# Shield_ver2.net
KiCad netlist of a schematic drawn in EAGLE
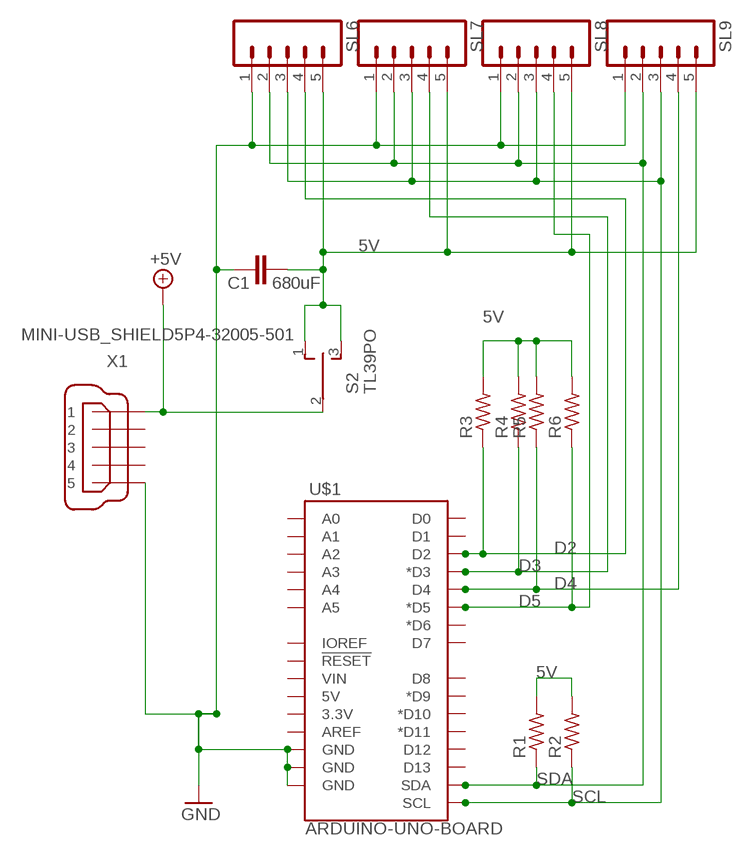
[diagram p0: schematic, sheet 1]

(export (version "E")
  (design (tool "Eeschema 10.0.6"))
  (components
    (comp (ref "C1")
      (value "680uF")
      (footprint "eagle-import:C5B2.5")
      (libsource (lib "eagle-import") (part "C5/2.5"))
    )
    (comp (ref "R1")
      (value "R-US_R0805")
      (footprint "eagle-import:R0805")
      (libsource (lib "eagle-import") (part "R-US_R0805"))
    )
    (comp (ref "R2")
      (value "R-US_R0805")
      (footprint "eagle-import:R0805")
      (libsource (lib "eagle-import") (part "R-US_R0805"))
    )
    (comp (ref "R3")
      (value "R-US_R0805")
      (footprint "eagle-import:R0805")
      (libsource (lib "eagle-import") (part "R-US_R0805"))
    )
    (comp (ref "R4")
      (value "R-US_R0805")
      (footprint "eagle-import:R0805")
      (libsource (lib "eagle-import") (part "R-US_R0805"))
    )
    (comp (ref "R5")
      (value "R-US_R0805")
      (footprint "eagle-import:R0805")
      (libsource (lib "eagle-import") (part "R-US_R0805"))
    )
    (comp (ref "R6")
      (value "R-US_R0805")
      (footprint "eagle-import:R0805")
      (libsource (lib "eagle-import") (part "R-US_R0805"))
    )
    (comp (ref "S2")
      (value "TL39PO")
      (footprint "eagle-import:TL3XPO")
      (libsource (lib "eagle-import") (part "TL39PO"))
    )
    (comp (ref "SL6")
      (value "M05")
      (footprint "eagle-import:05P")
      (libsource (lib "eagle-import") (part "M05"))
    )
    (comp (ref "SL7")
      (value "M05")
      (footprint "eagle-import:05P")
      (libsource (lib "eagle-import") (part "M05"))
    )
    (comp (ref "SL8")
      (value "M05")
      (footprint "eagle-import:05P")
      (libsource (lib "eagle-import") (part "M05"))
    )
    (comp (ref "SL9")
      (value "M05")
      (footprint "eagle-import:05P")
      (libsource (lib "eagle-import") (part "M05"))
    )
    (comp (ref "U$1")
      (value "ARDUINO-UNO-BOARD")
      (footprint "eagle-import:ARDUINO-UNO-BOARD")
      (libsource (lib "eagle-import") (part "ARDUINO-UNO-BOARD"))
    )
    (comp (ref "X1")
      (value "MINI-USB_SHIELD5P4-32005-501")
      (footprint "eagle-import:32005-501")
      (libsource (lib "eagle-import") (part "MINI-USB_SHIELD5P4-32005-501"))
    )
  )
  (nets
    (net (code "1") (name "+5V") (class "Default")
      (node (ref "S2") (pin "2") (pinfunction "P_2") (pintype "passive"))
      (node (ref "X1") (pin "1") (pinfunction "1_1") (pintype "passive"))
    )
    (net (code "2") (name "/5V") (class "Default")
      (node (ref "C1") (pin "2") (pinfunction "2_2") (pintype "passive"))
      (node (ref "R1") (pin "2") (pinfunction "2_2") (pintype "passive"))
      (node (ref "R2") (pin "2") (pinfunction "2_2") (pintype "passive"))
      (node (ref "R3") (pin "2") (pinfunction "2_2") (pintype "passive"))
      (node (ref "R4") (pin "2") (pinfunction "2_2") (pintype "passive"))
      (node (ref "R5") (pin "2") (pinfunction "2_2") (pintype "passive"))
      (node (ref "R6") (pin "2") (pinfunction "2_2") (pintype "passive"))
      (node (ref "S2") (pin "1") (pinfunction "O_1") (pintype "passive"))
      (node (ref "S2") (pin "3") (pinfunction "S_3") (pintype "passive"))
      (node (ref "SL6") (pin "5") (pinfunction "5_5") (pintype "passive"))
      (node (ref "SL7") (pin "5") (pinfunction "5_5") (pintype "passive"))
      (node (ref "SL8") (pin "5") (pinfunction "5_5") (pintype "passive"))
      (node (ref "SL9") (pin "5") (pinfunction "5_5") (pintype "passive"))
    )
    (net (code "3") (name "/D2") (class "Default")
      (node (ref "R3") (pin "1") (pinfunction "1_1") (pintype "passive"))
      (node (ref "SL6") (pin "4") (pinfunction "4_4") (pintype "passive"))
      (node (ref "U$1") (pin "D2") (pinfunction "D2_D2") (pintype "bidirectional"))
    )
    (net (code "4") (name "/D3") (class "Default")
      (node (ref "R4") (pin "1") (pinfunction "1_1") (pintype "passive"))
      (node (ref "SL7") (pin "4") (pinfunction "4_4") (pintype "passive"))
      (node (ref "U$1") (pin "D3") (pinfunction "*D3_D3") (pintype "bidirectional"))
    )
    (net (code "5") (name "/D4") (class "Default")
      (node (ref "R5") (pin "1") (pinfunction "1_1") (pintype "passive"))
      (node (ref "SL9") (pin "4") (pinfunction "4_4") (pintype "passive"))
      (node (ref "U$1") (pin "D4") (pinfunction "D4_D4") (pintype "bidirectional"))
    )
    (net (code "6") (name "/D5") (class "Default")
      (node (ref "R6") (pin "1") (pinfunction "1_1") (pintype "passive"))
      (node (ref "SL8") (pin "4") (pinfunction "4_4") (pintype "passive"))
      (node (ref "U$1") (pin "D5") (pinfunction "*D5_D5") (pintype "bidirectional"))
    )
    (net (code "7") (name "/SCL") (class "Default")
      (node (ref "R2") (pin "1") (pinfunction "1_1") (pintype "passive"))
      (node (ref "SL6") (pin "3") (pinfunction "3_3") (pintype "passive"))
      (node (ref "SL7") (pin "3") (pinfunction "3_3") (pintype "passive"))
      (node (ref "SL8") (pin "3") (pinfunction "3_3") (pintype "passive"))
      (node (ref "SL9") (pin "3") (pinfunction "3_3") (pintype "passive"))
      (node (ref "U$1") (pin "SCL") (pinfunction "SCL_SCL") (pintype "bidirectional"))
    )
    (net (code "8") (name "/SDA") (class "Default")
      (node (ref "R1") (pin "1") (pinfunction "1_1") (pintype "passive"))
      (node (ref "SL6") (pin "2") (pinfunction "2_2") (pintype "passive"))
      (node (ref "SL7") (pin "2") (pinfunction "2_2") (pintype "passive"))
      (node (ref "SL8") (pin "2") (pinfunction "2_2") (pintype "passive"))
      (node (ref "SL9") (pin "2") (pinfunction "2_2") (pintype "passive"))
      (node (ref "U$1") (pin "SDA") (pinfunction "SDA_SDA") (pintype "bidirectional"))
    )
    (net (code "9") (name "GND") (class "Default")
      (node (ref "C1") (pin "1") (pinfunction "1_1") (pintype "passive"))
      (node (ref "SL6") (pin "1") (pinfunction "1_1") (pintype "passive"))
      (node (ref "SL7") (pin "1") (pinfunction "1_1") (pintype "passive"))
      (node (ref "SL8") (pin "1") (pinfunction "1_1") (pintype "passive"))
      (node (ref "SL9") (pin "1") (pinfunction "1_1") (pintype "passive"))
      (node (ref "U$1") (pin "GND@1") (pinfunction "GND_GND@1") (pintype "bidirectional"))
      (node (ref "U$1") (pin "GND@2") (pinfunction "GND_GND@2") (pintype "bidirectional"))
      (node (ref "U$1") (pin "GND@3") (pinfunction "GND_GND@3") (pintype "bidirectional"))
      (node (ref "X1") (pin "5") (pinfunction "5_5") (pintype "passive"))
    )
    (net (code "10") (name "unconnected-(U$1-*D6-PadD6)") (class "Default")
      (node (ref "U$1") (pin "D6") (pinfunction "*D6_D6") (pintype "bidirectional"))
    )
    (net (code "11") (name "unconnected-(U$1-*D9-PadD9)") (class "Default")
      (node (ref "U$1") (pin "D9") (pinfunction "*D9_D9") (pintype "bidirectional"))
    )
    (net (code "12") (name "unconnected-(U$1-*D10-PadD10)") (class "Default")
      (node (ref "U$1") (pin "D10") (pinfunction "*D10_D10") (pintype "bidirectional"))
    )
    (net (code "13") (name "unconnected-(U$1-*D11-PadD11)") (class "Default")
      (node (ref "U$1") (pin "D11") (pinfunction "*D11_D11") (pintype "bidirectional"))
    )
    (net (code "14") (name "unconnected-(U$1-Pad3.3V)") (class "Default")
      (node (ref "U$1") (pin "3.3V") (pinfunction "3.3V_3.3V") (pintype "bidirectional"))
    )
    (net (code "15") (name "unconnected-(U$1-Pad5V)") (class "Default")
      (node (ref "U$1") (pin "5V") (pinfunction "5V_5V") (pintype "bidirectional"))
    )
    (net (code "16") (name "unconnected-(U$1-PadA0)") (class "Default")
      (node (ref "U$1") (pin "A0") (pinfunction "A0_A0") (pintype "bidirectional"))
    )
    (net (code "17") (name "unconnected-(U$1-PadA1)") (class "Default")
      (node (ref "U$1") (pin "A1") (pinfunction "A1_A1") (pintype "bidirectional"))
    )
    (net (code "18") (name "unconnected-(U$1-PadA2)") (class "Default")
      (node (ref "U$1") (pin "A2") (pinfunction "A2_A2") (pintype "bidirectional"))
    )
    (net (code "19") (name "unconnected-(U$1-PadA3)") (class "Default")
      (node (ref "U$1") (pin "A3") (pinfunction "A3_A3") (pintype "bidirectional"))
    )
    (net (code "20") (name "unconnected-(U$1-PadA4)") (class "Default")
      (node (ref "U$1") (pin "A4") (pinfunction "A4_A4") (pintype "bidirectional"))
    )
    (net (code "21") (name "unconnected-(U$1-PadA5)") (class "Default")
      (node (ref "U$1") (pin "A5") (pinfunction "A5_A5") (pintype "bidirectional"))
    )
    (net (code "22") (name "unconnected-(U$1-PadAREF)") (class "Default")
      (node (ref "U$1") (pin "AREF") (pinfunction "AREF_AREF") (pintype "bidirectional"))
    )
    (net (code "23") (name "unconnected-(U$1-PadD0)") (class "Default")
      (node (ref "U$1") (pin "D0") (pinfunction "D0_D0") (pintype "bidirectional"))
    )
    (net (code "24") (name "unconnected-(U$1-PadD1)") (class "Default")
      (node (ref "U$1") (pin "D1") (pinfunction "D1_D1") (pintype "bidirectional"))
    )
    (net (code "25") (name "unconnected-(U$1-PadD7)") (class "Default")
      (node (ref "U$1") (pin "D7") (pinfunction "D7_D7") (pintype "bidirectional"))
    )
    (net (code "26") (name "unconnected-(U$1-PadD8)") (class "Default")
      (node (ref "U$1") (pin "D8") (pinfunction "D8_D8") (pintype "bidirectional"))
    )
    (net (code "27") (name "unconnected-(U$1-PadD12)") (class "Default")
      (node (ref "U$1") (pin "D12") (pinfunction "D12_D12") (pintype "bidirectional"))
    )
    (net (code "28") (name "unconnected-(U$1-PadD13)") (class "Default")
      (node (ref "U$1") (pin "D13") (pinfunction "D13_D13") (pintype "bidirectional"))
    )
    (net (code "29") (name "unconnected-(U$1-PadIOREF)") (class "Default")
      (node (ref "U$1") (pin "IOREF") (pinfunction "IOREF_IOREF") (pintype "bidirectional"))
    )
    (net (code "30") (name "unconnected-(U$1-PadVIN)") (class "Default")
      (node (ref "U$1") (pin "VIN") (pinfunction "VIN_VIN") (pintype "bidirectional"))
    )
    (net (code "31") (name "unconnected-(U$1-~{RESET}-PadRESET@1)") (class "Default")
      (node (ref "U$1") (pin "RESET@1") (pinfunction "~{RESET}_RESET@1") (pintype "bidirectional"))
    )
    (net (code "32") (name "unconnected-(X1-Pad2)") (class "Default")
      (node (ref "X1") (pin "2") (pinfunction "2_2") (pintype "passive"))
    )
    (net (code "33") (name "unconnected-(X1-Pad3)") (class "Default")
      (node (ref "X1") (pin "3") (pinfunction "3_3") (pintype "passive"))
    )
    (net (code "34") (name "unconnected-(X1-Pad4)") (class "Default")
      (node (ref "X1") (pin "4") (pinfunction "4_4") (pintype "passive"))
    )
  )
)
